# test.net
KiCad netlist of a schematic drawn in EAGLE
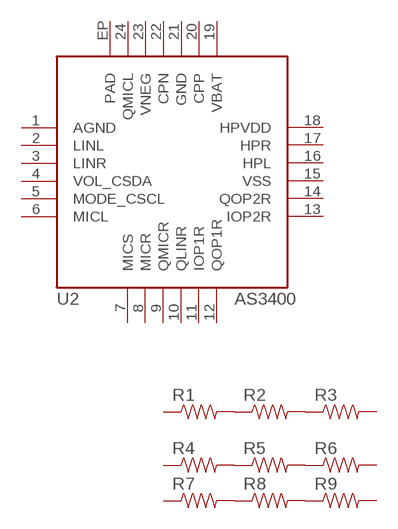
[diagram p0: schematic, sheet 1]

(export (version "E")
  (design (tool "Eeschema 10.0.6"))
  (components
    (comp (ref "R1")
      (value "RESISTOR0805-RES")
      (footprint "eagle-import:0805")
      (libsource (lib "eagle-import") (part "RESISTOR0805-RES"))
    )
    (comp (ref "R2")
      (value "RESISTOR0805-RES")
      (footprint "eagle-import:0805")
      (libsource (lib "eagle-import") (part "RESISTOR0805-RES"))
    )
    (comp (ref "R3")
      (value "RESISTOR0805-RES")
      (footprint "eagle-import:0805")
      (libsource (lib "eagle-import") (part "RESISTOR0805-RES"))
    )
    (comp (ref "R4")
      (value "RESISTOR0603-RES")
      (footprint "eagle-import:0603-RES")
      (libsource (lib "eagle-import") (part "RESISTOR0603-RES"))
    )
    (comp (ref "R5")
      (value "RESISTOR0603-RES")
      (footprint "eagle-import:0603-RES")
      (libsource (lib "eagle-import") (part "RESISTOR0603-RES"))
    )
    (comp (ref "R6")
      (value "RESISTOR0603-RES")
      (footprint "eagle-import:0603-RES")
      (libsource (lib "eagle-import") (part "RESISTOR0603-RES"))
    )
    (comp (ref "R7")
      (value "RESISTOR0402-RES")
      (footprint "eagle-import:0402-RES")
      (libsource (lib "eagle-import") (part "RESISTOR0402-RES"))
    )
    (comp (ref "R8")
      (value "RESISTOR0402-RES")
      (footprint "eagle-import:0402-RES")
      (libsource (lib "eagle-import") (part "RESISTOR0402-RES"))
    )
    (comp (ref "R9")
      (value "RESISTOR0402-RES")
      (footprint "eagle-import:0402-RES")
      (libsource (lib "eagle-import") (part "RESISTOR0402-RES"))
    )
    (comp (ref "U2")
      (value "AS3400")
      (footprint "eagle-import:QFN-24_ALT2")
      (libsource (lib "eagle-import") (part "AS3400"))
    )
  )
  (nets
    (net (code "1") (name "Net-(R1-Pad2)") (class "Default")
      (node (ref "R1") (pin "2") (pinfunction "2_2") (pintype "passive"))
      (node (ref "R2") (pin "1") (pinfunction "1_1") (pintype "passive"))
    )
    (net (code "2") (name "Net-(R2-Pad2)") (class "Default")
      (node (ref "R2") (pin "2") (pinfunction "2_2") (pintype "passive"))
      (node (ref "R3") (pin "1") (pinfunction "1_1") (pintype "passive"))
    )
    (net (code "3") (name "Net-(R4-Pad2)") (class "Default")
      (node (ref "R4") (pin "2") (pinfunction "2_2") (pintype "passive"))
      (node (ref "R5") (pin "1") (pinfunction "1_1") (pintype "passive"))
    )
    (net (code "4") (name "Net-(R5-Pad2)") (class "Default")
      (node (ref "R5") (pin "2") (pinfunction "2_2") (pintype "passive"))
      (node (ref "R6") (pin "1") (pinfunction "1_1") (pintype "passive"))
    )
    (net (code "5") (name "Net-(R7-Pad2)") (class "Default")
      (node (ref "R7") (pin "2") (pinfunction "2_2") (pintype "passive"))
      (node (ref "R8") (pin "1") (pinfunction "1_1") (pintype "passive"))
    )
    (net (code "6") (name "Net-(R8-Pad2)") (class "Default")
      (node (ref "R8") (pin "2") (pinfunction "2_2") (pintype "passive"))
      (node (ref "R9") (pin "1") (pinfunction "1_1") (pintype "passive"))
    )
    (net (code "7") (name "unconnected-(R1-Pad1)") (class "Default")
      (node (ref "R1") (pin "1") (pinfunction "1_1") (pintype "passive"))
    )
    (net (code "8") (name "unconnected-(R3-Pad2)") (class "Default")
      (node (ref "R3") (pin "2") (pinfunction "2_2") (pintype "passive"))
    )
    (net (code "9") (name "unconnected-(R4-Pad1)") (class "Default")
      (node (ref "R4") (pin "1") (pinfunction "1_1") (pintype "passive"))
    )
    (net (code "10") (name "unconnected-(R6-Pad2)") (class "Default")
      (node (ref "R6") (pin "2") (pinfunction "2_2") (pintype "passive"))
    )
    (net (code "11") (name "unconnected-(R7-Pad1)") (class "Default")
      (node (ref "R7") (pin "1") (pinfunction "1_1") (pintype "passive"))
    )
    (net (code "12") (name "unconnected-(R9-Pad2)") (class "Default")
      (node (ref "R9") (pin "2") (pinfunction "2_2") (pintype "passive"))
    )
    (net (code "13") (name "unconnected-(U2-AGND-Pad1)") (class "Default")
      (node (ref "U2") (pin "1") (pinfunction "AGND_1") (pintype "bidirectional"))
    )
    (net (code "14") (name "unconnected-(U2-CPN-Pad22)") (class "Default")
      (node (ref "U2") (pin "22") (pinfunction "CPN_22") (pintype "bidirectional"))
    )
    (net (code "15") (name "unconnected-(U2-CPP-Pad20)") (class "Default")
      (node (ref "U2") (pin "20") (pinfunction "CPP_20") (pintype "bidirectional"))
    )
    (net (code "16") (name "unconnected-(U2-GND-Pad21)") (class "Default")
      (node (ref "U2") (pin "21") (pinfunction "GND_21") (pintype "bidirectional"))
    )
    (net (code "17") (name "unconnected-(U2-HPL-Pad16)") (class "Default")
      (node (ref "U2") (pin "16") (pinfunction "HPL_16") (pintype "bidirectional"))
    )
    (net (code "18") (name "unconnected-(U2-HPR-Pad17)") (class "Default")
      (node (ref "U2") (pin "17") (pinfunction "HPR_17") (pintype "bidirectional"))
    )
    (net (code "19") (name "unconnected-(U2-HPVDD-Pad18)") (class "Default")
      (node (ref "U2") (pin "18") (pinfunction "HPVDD_18") (pintype "bidirectional"))
    )
    (net (code "20") (name "unconnected-(U2-IOP1R-Pad11)") (class "Default")
      (node (ref "U2") (pin "11") (pinfunction "IOP1R_11") (pintype "bidirectional"))
    )
    (net (code "21") (name "unconnected-(U2-IOP2R-Pad13)") (class "Default")
      (node (ref "U2") (pin "13") (pinfunction "IOP2R_13") (pintype "bidirectional"))
    )
    (net (code "22") (name "unconnected-(U2-LINL-Pad2)") (class "Default")
      (node (ref "U2") (pin "2") (pinfunction "LINL_2") (pintype "bidirectional"))
    )
    (net (code "23") (name "unconnected-(U2-LINR-Pad3)") (class "Default")
      (node (ref "U2") (pin "3") (pinfunction "LINR_3") (pintype "bidirectional"))
    )
    (net (code "24") (name "unconnected-(U2-MICL-Pad6)") (class "Default")
      (node (ref "U2") (pin "6") (pinfunction "MICL_6") (pintype "bidirectional"))
    )
    (net (code "25") (name "unconnected-(U2-MICR-Pad8)") (class "Default")
      (node (ref "U2") (pin "8") (pinfunction "MICR_8") (pintype "bidirectional"))
    )
    (net (code "26") (name "unconnected-(U2-MICS-Pad7)") (class "Default")
      (node (ref "U2") (pin "7") (pinfunction "MICS_7") (pintype "bidirectional"))
    )
    (net (code "27") (name "unconnected-(U2-MODE_CSCL-Pad5)") (class "Default")
      (node (ref "U2") (pin "5") (pinfunction "MODE_CSCL_5") (pintype "bidirectional"))
    )
    (net (code "28") (name "unconnected-(U2-PAD-PadEP)") (class "Default")
      (node (ref "U2") (pin "EP") (pinfunction "PAD_EP") (pintype "bidirectional"))
    )
    (net (code "29") (name "unconnected-(U2-QLINR-Pad10)") (class "Default")
      (node (ref "U2") (pin "10") (pinfunction "QLINR_10") (pintype "bidirectional"))
    )
    (net (code "30") (name "unconnected-(U2-QMICL-Pad24)") (class "Default")
      (node (ref "U2") (pin "24") (pinfunction "QMICL_24") (pintype "bidirectional"))
    )
    (net (code "31") (name "unconnected-(U2-QMICR-Pad9)") (class "Default")
      (node (ref "U2") (pin "9") (pinfunction "QMICR_9") (pintype "bidirectional"))
    )
    (net (code "32") (name "unconnected-(U2-QOP1R-Pad12)") (class "Default")
      (node (ref "U2") (pin "12") (pinfunction "QOP1R_12") (pintype "bidirectional"))
    )
    (net (code "33") (name "unconnected-(U2-QOP2R-Pad14)") (class "Default")
      (node (ref "U2") (pin "14") (pinfunction "QOP2R_14") (pintype "bidirectional"))
    )
    (net (code "34") (name "unconnected-(U2-VBAT-Pad19)") (class "Default")
      (node (ref "U2") (pin "19") (pinfunction "VBAT_19") (pintype "bidirectional"))
    )
    (net (code "35") (name "unconnected-(U2-VNEG-Pad23)") (class "Default")
      (node (ref "U2") (pin "23") (pinfunction "VNEG_23") (pintype "bidirectional"))
    )
    (net (code "36") (name "unconnected-(U2-VOL_CSDA-Pad4)") (class "Default")
      (node (ref "U2") (pin "4") (pinfunction "VOL_CSDA_4") (pintype "bidirectional"))
    )
    (net (code "37") (name "unconnected-(U2-VSS-Pad15)") (class "Default")
      (node (ref "U2") (pin "15") (pinfunction "VSS_15") (pintype "bidirectional"))
    )
  )
)
